# ZYNQ_POWER.net
KiCad netlist of a schematic drawn in Altium Designer
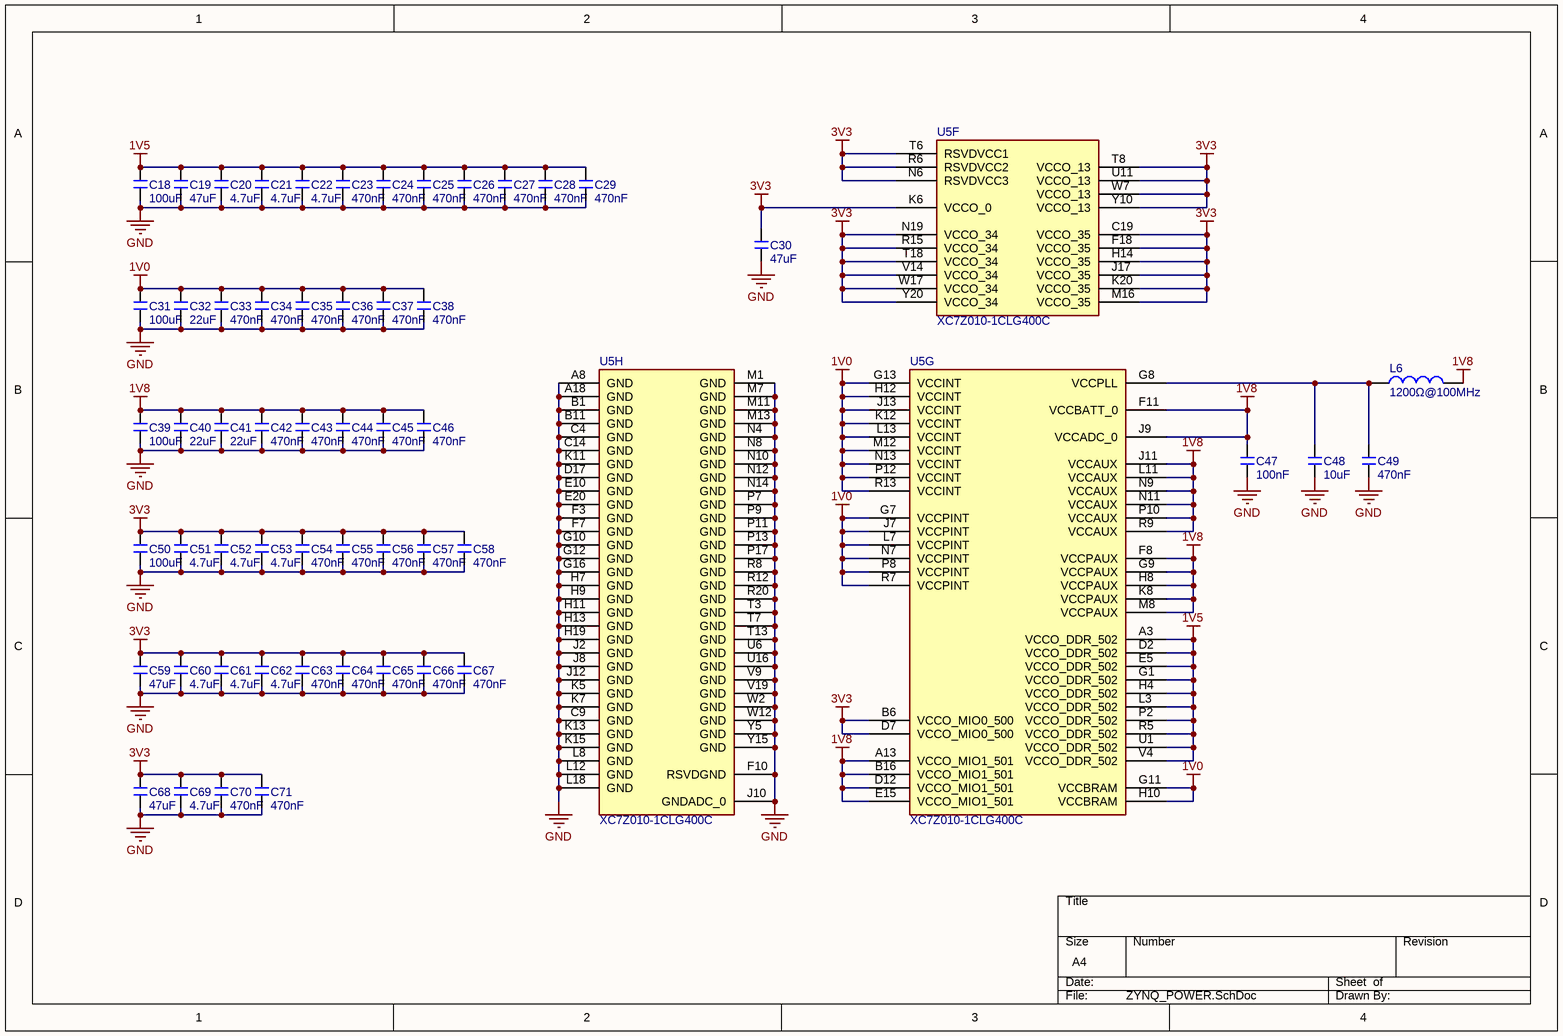
[diagram p0: ZYNQ_POWER.SchDoc]

(export (version "E")
  (design (tool "Eeschema 10.0.6"))
  (components
    (comp (ref "C18")
      (value "100uF")
      (footprint "C 0805_L")
      (description "无极性贴片电容")
      (fields (field (name "版权归属") "源创客"))
      (libsource (lib "3.1   - 电阻-电容-电感") (part "C"))
    )
    (comp (ref "C19")
      (value "47uF")
      (footprint "C 0805_L")
      (description "无极性贴片电容")
      (fields (field (name "版权归属") "源创客"))
      (libsource (lib "3.1   - 电阻-电容-电感") (part "C"))
    )
    (comp (ref "C20")
      (value "4.7uF")
      (footprint "C 0603_L")
      (description "无极性贴片电容")
      (fields (field (name "版权归属") "源创客"))
      (libsource (lib "3.1   - 电阻-电容-电感") (part "C"))
    )
    (comp (ref "C21")
      (value "4.7uF")
      (footprint "C 0603_L")
      (description "无极性贴片电容")
      (fields (field (name "版权归属") "源创客"))
      (libsource (lib "3.1   - 电阻-电容-电感") (part "C"))
    )
    (comp (ref "C22")
      (value "4.7uF")
      (footprint "C 0603_L")
      (description "无极性贴片电容")
      (fields (field (name "版权归属") "源创客"))
      (libsource (lib "3.1   - 电阻-电容-电感") (part "C"))
    )
    (comp (ref "C23")
      (value "470nF")
      (footprint "C 0805_L")
      (description "无极性贴片电容")
      (fields (field (name "版权归属") "源创客"))
      (libsource (lib "3.1   - 电阻-电容-电感") (part "C"))
    )
    (comp (ref "C24")
      (value "470nF")
      (footprint "C 0805_L")
      (description "无极性贴片电容")
      (fields (field (name "版权归属") "源创客"))
      (libsource (lib "3.1   - 电阻-电容-电感") (part "C"))
    )
    (comp (ref "C25")
      (value "470nF")
      (footprint "C 0805_L")
      (description "无极性贴片电容")
      (fields (field (name "版权归属") "源创客"))
      (libsource (lib "3.1   - 电阻-电容-电感") (part "C"))
    )
    (comp (ref "C26")
      (value "470nF")
      (footprint "C 0805_L")
      (description "无极性贴片电容")
      (fields (field (name "版权归属") "源创客"))
      (libsource (lib "3.1   - 电阻-电容-电感") (part "C"))
    )
    (comp (ref "C27")
      (value "470nF")
      (footprint "C 0805_L")
      (description "无极性贴片电容")
      (fields (field (name "版权归属") "源创客"))
      (libsource (lib "3.1   - 电阻-电容-电感") (part "C"))
    )
    (comp (ref "C28")
      (value "470nF")
      (footprint "C 0805_L")
      (description "无极性贴片电容")
      (fields (field (name "版权归属") "源创客"))
      (libsource (lib "3.1   - 电阻-电容-电感") (part "C"))
    )
    (comp (ref "C29")
      (value "470nF")
      (footprint "C 0805_L")
      (description "无极性贴片电容")
      (fields (field (name "版权归属") "源创客"))
      (libsource (lib "3.1   - 电阻-电容-电感") (part "C"))
    )
    (comp (ref "C30")
      (value "47uF")
      (footprint "C 0805_L")
      (description "无极性贴片电容")
      (fields (field (name "版权归属") "源创客"))
      (libsource (lib "3.1   - 电阻-电容-电感") (part "C"))
    )
    (comp (ref "C31")
      (value "100uF")
      (footprint "C 0805_L")
      (description "无极性贴片电容")
      (fields (field (name "版权归属") "源创客"))
      (libsource (lib "3.1   - 电阻-电容-电感") (part "C"))
    )
    (comp (ref "C32")
      (value "22uF")
      (footprint "C 0805_L")
      (description "无极性贴片电容")
      (fields (field (name "版权归属") "源创客"))
      (libsource (lib "3.1   - 电阻-电容-电感") (part "C"))
    )
    (comp (ref "C33")
      (value "470nF")
      (footprint "C 0805_L")
      (description "无极性贴片电容")
      (fields (field (name "版权归属") "源创客"))
      (libsource (lib "3.1   - 电阻-电容-电感") (part "C"))
    )
    (comp (ref "C34")
      (value "470nF")
      (footprint "C 0805_L")
      (description "无极性贴片电容")
      (fields (field (name "版权归属") "源创客"))
      (libsource (lib "3.1   - 电阻-电容-电感") (part "C"))
    )
    (comp (ref "C35")
      (value "470nF")
      (footprint "C 0805_L")
      (description "无极性贴片电容")
      (fields (field (name "版权归属") "源创客"))
      (libsource (lib "3.1   - 电阻-电容-电感") (part "C"))
    )
    (comp (ref "C36")
      (value "470nF")
      (footprint "C 0805_L")
      (description "无极性贴片电容")
      (fields (field (name "版权归属") "源创客"))
      (libsource (lib "3.1   - 电阻-电容-电感") (part "C"))
    )
    (comp (ref "C37")
      (value "470nF")
      (footprint "C 0805_L")
      (description "无极性贴片电容")
      (fields (field (name "版权归属") "源创客"))
      (libsource (lib "3.1   - 电阻-电容-电感") (part "C"))
    )
    (comp (ref "C38")
      (value "470nF")
      (footprint "C 0805_L")
      (description "无极性贴片电容")
      (fields (field (name "版权归属") "源创客"))
      (libsource (lib "3.1   - 电阻-电容-电感") (part "C"))
    )
    (comp (ref "C39")
      (value "100uF")
      (footprint "C 0805_L")
      (description "无极性贴片电容")
      (fields (field (name "版权归属") "源创客"))
      (libsource (lib "3.1   - 电阻-电容-电感") (part "C"))
    )
    (comp (ref "C40")
      (value "22uF")
      (footprint "C 0805_L")
      (description "无极性贴片电容")
      (fields (field (name "版权归属") "源创客"))
      (libsource (lib "3.1   - 电阻-电容-电感") (part "C"))
    )
    (comp (ref "C41")
      (value "22uF")
      (footprint "C 0805_L")
      (description "无极性贴片电容")
      (fields (field (name "版权归属") "源创客"))
      (libsource (lib "3.1   - 电阻-电容-电感") (part "C"))
    )
    (comp (ref "C42")
      (value "470nF")
      (footprint "C 0805_L")
      (description "无极性贴片电容")
      (fields (field (name "版权归属") "源创客"))
      (libsource (lib "3.1   - 电阻-电容-电感") (part "C"))
    )
    (comp (ref "C43")
      (value "470nF")
      (footprint "C 0805_L")
      (description "无极性贴片电容")
      (fields (field (name "版权归属") "源创客"))
      (libsource (lib "3.1   - 电阻-电容-电感") (part "C"))
    )
    (comp (ref "C44")
      (value "470nF")
      (footprint "C 0805_L")
      (description "无极性贴片电容")
      (fields (field (name "版权归属") "源创客"))
      (libsource (lib "3.1   - 电阻-电容-电感") (part "C"))
    )
    (comp (ref "C45")
      (value "470nF")
      (footprint "C 0805_L")
      (description "无极性贴片电容")
      (fields (field (name "版权归属") "源创客"))
      (libsource (lib "3.1   - 电阻-电容-电感") (part "C"))
    )
    (comp (ref "C46")
      (value "470nF")
      (footprint "C 0805_L")
      (description "无极性贴片电容")
      (fields (field (name "版权归属") "源创客"))
      (libsource (lib "3.1   - 电阻-电容-电感") (part "C"))
    )
    (comp (ref "C47")
      (value "100nF")
      (footprint "C 0402_L")
      (description "无极性贴片电容")
      (fields (field (name "版权归属") "源创客"))
      (libsource (lib "3.1   - 电阻-电容-电感") (part "C"))
    )
    (comp (ref "C48")
      (value "10uF")
      (footprint "C 0603_L")
      (description "无极性贴片电容")
      (fields (field (name "版权归属") "源创客"))
      (libsource (lib "3.1   - 电阻-电容-电感") (part "C"))
    )
    (comp (ref "C49")
      (value "470nF")
      (footprint "C 0805_L")
      (description "无极性贴片电容")
      (fields (field (name "版权归属") "源创客"))
      (libsource (lib "3.1   - 电阻-电容-电感") (part "C"))
    )
    (comp (ref "C50")
      (value "100uF")
      (footprint "C 0805_L")
      (description "无极性贴片电容")
      (fields (field (name "版权归属") "源创客"))
      (libsource (lib "3.1   - 电阻-电容-电感") (part "C"))
    )
    (comp (ref "C51")
      (value "4.7uF")
      (footprint "C 0603_L")
      (description "无极性贴片电容")
      (fields (field (name "版权归属") "源创客"))
      (libsource (lib "3.1   - 电阻-电容-电感") (part "C"))
    )
    (comp (ref "C52")
      (value "4.7uF")
      (footprint "C 0603_L")
      (description "无极性贴片电容")
      (fields (field (name "版权归属") "源创客"))
      (libsource (lib "3.1   - 电阻-电容-电感") (part "C"))
    )
    (comp (ref "C53")
      (value "4.7uF")
      (footprint "C 0603_L")
      (description "无极性贴片电容")
      (fields (field (name "版权归属") "源创客"))
      (libsource (lib "3.1   - 电阻-电容-电感") (part "C"))
    )
    (comp (ref "C54")
      (value "470nF")
      (footprint "C 0805_L")
      (description "无极性贴片电容")
      (fields (field (name "版权归属") "源创客"))
      (libsource (lib "3.1   - 电阻-电容-电感") (part "C"))
    )
    (comp (ref "C55")
      (value "470nF")
      (footprint "C 0805_L")
      (description "无极性贴片电容")
      (fields (field (name "版权归属") "源创客"))
      (libsource (lib "3.1   - 电阻-电容-电感") (part "C"))
    )
    (comp (ref "C56")
      (value "470nF")
      (footprint "C 0805_L")
      (description "无极性贴片电容")
      (fields (field (name "版权归属") "源创客"))
      (libsource (lib "3.1   - 电阻-电容-电感") (part "C"))
    )
    (comp (ref "C57")
      (value "470nF")
      (footprint "C 0805_L")
      (description "无极性贴片电容")
      (fields (field (name "版权归属") "源创客"))
      (libsource (lib "3.1   - 电阻-电容-电感") (part "C"))
    )
    (comp (ref "C58")
      (value "470nF")
      (footprint "C 0805_L")
      (description "无极性贴片电容")
      (fields (field (name "版权归属") "源创客"))
      (libsource (lib "3.1   - 电阻-电容-电感") (part "C"))
    )
    (comp (ref "C59")
      (value "47uF")
      (footprint "C 0805_L")
      (description "无极性贴片电容")
      (fields (field (name "版权归属") "源创客"))
      (libsource (lib "3.1   - 电阻-电容-电感") (part "C"))
    )
    (comp (ref "C60")
      (value "4.7uF")
      (footprint "C 0603_L")
      (description "无极性贴片电容")
      (fields (field (name "版权归属") "源创客"))
      (libsource (lib "3.1   - 电阻-电容-电感") (part "C"))
    )
    (comp (ref "C61")
      (value "4.7uF")
      (footprint "C 0603_L")
      (description "无极性贴片电容")
      (fields (field (name "版权归属") "源创客"))
      (libsource (lib "3.1   - 电阻-电容-电感") (part "C"))
    )
    (comp (ref "C62")
      (value "4.7uF")
      (footprint "C 0603_L")
      (description "无极性贴片电容")
      (fields (field (name "版权归属") "源创客"))
      (libsource (lib "3.1   - 电阻-电容-电感") (part "C"))
    )
    (comp (ref "C63")
      (value "470nF")
      (footprint "C 0805_L")
      (description "无极性贴片电容")
      (fields (field (name "版权归属") "源创客"))
      (libsource (lib "3.1   - 电阻-电容-电感") (part "C"))
    )
    (comp (ref "C64")
      (value "470nF")
      (footprint "C 0805_L")
      (description "无极性贴片电容")
      (fields (field (name "版权归属") "源创客"))
      (libsource (lib "3.1   - 电阻-电容-电感") (part "C"))
    )
    (comp (ref "C65")
      (value "470nF")
      (footprint "C 0805_L")
      (description "无极性贴片电容")
      (fields (field (name "版权归属") "源创客"))
      (libsource (lib "3.1   - 电阻-电容-电感") (part "C"))
    )
    (comp (ref "C66")
      (value "470nF")
      (footprint "C 0805_L")
      (description "无极性贴片电容")
      (fields (field (name "版权归属") "源创客"))
      (libsource (lib "3.1   - 电阻-电容-电感") (part "C"))
    )
    (comp (ref "C67")
      (value "470nF")
      (footprint "C 0805_L")
      (description "无极性贴片电容")
      (fields (field (name "版权归属") "源创客"))
      (libsource (lib "3.1   - 电阻-电容-电感") (part "C"))
    )
    (comp (ref "C68")
      (value "47uF")
      (footprint "C 0805_L")
      (description "无极性贴片电容")
      (fields (field (name "版权归属") "源创客"))
      (libsource (lib "3.1   - 电阻-电容-电感") (part "C"))
    )
    (comp (ref "C69")
      (value "4.7uF")
      (footprint "C 0603_L")
      (description "无极性贴片电容")
      (fields (field (name "版权归属") "源创客"))
      (libsource (lib "3.1   - 电阻-电容-电感") (part "C"))
    )
    (comp (ref "C70")
      (value "470nF")
      (footprint "C 0805_L")
      (description "无极性贴片电容")
      (fields (field (name "版权归属") "源创客"))
      (libsource (lib "3.1   - 电阻-电容-电感") (part "C"))
    )
    (comp (ref "C71")
      (value "470nF")
      (footprint "C 0805_L")
      (description "无极性贴片电容")
      (fields (field (name "版权归属") "源创客"))
      (libsource (lib "3.1   - 电阻-电容-电感") (part "C"))
    )
    (comp (ref "L6")
      (value "1200Ω@100MHz")
      (footprint "L 0805")
      (description "小功率贴片电感")
      (fields (field (name "版权归属") "源创客"))
      (libsource (lib "3.1   - 电阻-电容-电感") (part "L"))
    )
    (comp (ref "U5")
      (value "XC7Z010-1CLG400C")
      (footprint "CLG400")
      (description "ZYNQ7000芯片")
      (libsource (lib "16.2 - Xilinx芯片") (part "XC7Z010-1CLG400C"))
    )
  )
  (nets
    (net (code "1") (name "1V0") (class "Default")
      (node (ref "C31") (pin "1") (pinfunction "1_1") (pintype "passive"))
      (node (ref "C32") (pin "2") (pinfunction "2_2") (pintype "passive"))
      (node (ref "C33") (pin "2") (pinfunction "2_2") (pintype "passive"))
      (node (ref "C34") (pin "2") (pinfunction "2_2") (pintype "passive"))
      (node (ref "C35") (pin "2") (pinfunction "2_2") (pintype "passive"))
      (node (ref "C36") (pin "2") (pinfunction "2_2") (pintype "passive"))
      (node (ref "C37") (pin "2") (pinfunction "2_2") (pintype "passive"))
      (node (ref "C38") (pin "2") (pinfunction "2_2") (pintype "passive"))
      (node (ref "U5") (pin "G11") (pinfunction "VCCBRAM_G11") (pintype "power_in"))
      (node (ref "U5") (pin "G13") (pinfunction "VCCINT_G13") (pintype "power_in"))
      (node (ref "U5") (pin "G7") (pinfunction "VCCPINT_G7") (pintype "power_in"))
      (node (ref "U5") (pin "H10") (pinfunction "VCCBRAM_H10") (pintype "power_in"))
      (node (ref "U5") (pin "H12") (pinfunction "VCCINT_H12") (pintype "power_in"))
      (node (ref "U5") (pin "J13") (pinfunction "VCCINT_J13") (pintype "power_in"))
      (node (ref "U5") (pin "J7") (pinfunction "VCCPINT_J7") (pintype "power_in"))
      (node (ref "U5") (pin "K12") (pinfunction "VCCINT_K12") (pintype "power_in"))
      (node (ref "U5") (pin "L13") (pinfunction "VCCINT_L13") (pintype "power_in"))
      (node (ref "U5") (pin "L7") (pinfunction "VCCPINT_L7") (pintype "power_in"))
      (node (ref "U5") (pin "M12") (pinfunction "VCCINT_M12") (pintype "power_in"))
      (node (ref "U5") (pin "N13") (pinfunction "VCCINT_N13") (pintype "power_in"))
      (node (ref "U5") (pin "N7") (pinfunction "VCCPINT_N7") (pintype "power_in"))
      (node (ref "U5") (pin "P12") (pinfunction "VCCINT_P12") (pintype "power_in"))
      (node (ref "U5") (pin "P8") (pinfunction "VCCPINT_P8") (pintype "power_in"))
      (node (ref "U5") (pin "R13") (pinfunction "VCCINT_R13") (pintype "power_in"))
      (node (ref "U5") (pin "R7") (pinfunction "VCCPINT_R7") (pintype "power_in"))
    )
    (net (code "2") (name "1V5") (class "Default")
      (node (ref "C18") (pin "1") (pinfunction "1_1") (pintype "passive"))
      (node (ref "C19") (pin "2") (pinfunction "2_2") (pintype "passive"))
      (node (ref "C20") (pin "2") (pinfunction "2_2") (pintype "passive"))
      (node (ref "C21") (pin "2") (pinfunction "2_2") (pintype "passive"))
      (node (ref "C22") (pin "2") (pinfunction "2_2") (pintype "passive"))
      (node (ref "C23") (pin "2") (pinfunction "2_2") (pintype "passive"))
      (node (ref "C24") (pin "2") (pinfunction "2_2") (pintype "passive"))
      (node (ref "C25") (pin "2") (pinfunction "2_2") (pintype "passive"))
      (node (ref "C26") (pin "2") (pinfunction "2_2") (pintype "passive"))
      (node (ref "C27") (pin "2") (pinfunction "2_2") (pintype "passive"))
      (node (ref "C28") (pin "2") (pinfunction "2_2") (pintype "passive"))
      (node (ref "C29") (pin "2") (pinfunction "2_2") (pintype "passive"))
      (node (ref "U5") (pin "A3") (pinfunction "VCCO_DDR_502_A3") (pintype "power_in"))
      (node (ref "U5") (pin "D2") (pinfunction "VCCO_DDR_502_D2") (pintype "power_in"))
      (node (ref "U5") (pin "E5") (pinfunction "VCCO_DDR_502_E5") (pintype "power_in"))
      (node (ref "U5") (pin "G1") (pinfunction "VCCO_DDR_502_G1") (pintype "power_in"))
      (node (ref "U5") (pin "H4") (pinfunction "VCCO_DDR_502_H4") (pintype "power_in"))
      (node (ref "U5") (pin "L3") (pinfunction "VCCO_DDR_502_L3") (pintype "power_in"))
      (node (ref "U5") (pin "P2") (pinfunction "VCCO_DDR_502_P2") (pintype "power_in"))
      (node (ref "U5") (pin "R5") (pinfunction "VCCO_DDR_502_R5") (pintype "power_in"))
      (node (ref "U5") (pin "U1") (pinfunction "VCCO_DDR_502_U1") (pintype "power_in"))
      (node (ref "U5") (pin "V4") (pinfunction "VCCO_DDR_502_V4") (pintype "power_in"))
    )
    (net (code "3") (name "1V8") (class "Default")
      (node (ref "C39") (pin "1") (pinfunction "1_1") (pintype "passive"))
      (node (ref "C40") (pin "2") (pinfunction "2_2") (pintype "passive"))
      (node (ref "C41") (pin "2") (pinfunction "2_2") (pintype "passive"))
      (node (ref "C42") (pin "2") (pinfunction "2_2") (pintype "passive"))
      (node (ref "C43") (pin "2") (pinfunction "2_2") (pintype "passive"))
      (node (ref "C44") (pin "2") (pinfunction "2_2") (pintype "passive"))
      (node (ref "C45") (pin "2") (pinfunction "2_2") (pintype "passive"))
      (node (ref "C46") (pin "2") (pinfunction "2_2") (pintype "passive"))
      (node (ref "C47") (pin "2") (pinfunction "2_2") (pintype "passive"))
      (node (ref "L6") (pin "2") (pinfunction "2_2") (pintype "passive"))
      (node (ref "U5") (pin "A13") (pinfunction "VCCO_MIO1_501_A13") (pintype "power_in"))
      (node (ref "U5") (pin "B16") (pinfunction "VCCO_MIO1_501_B16") (pintype "power_in"))
      (node (ref "U5") (pin "D12") (pinfunction "VCCO_MIO1_501_D12") (pintype "power_in"))
      (node (ref "U5") (pin "E15") (pinfunction "VCCO_MIO1_501_E15") (pintype "power_in"))
      (node (ref "U5") (pin "F11") (pinfunction "VCCBATT_0_F11") (pintype "power_in"))
      (node (ref "U5") (pin "F8") (pinfunction "VCCPAUX_F8") (pintype "power_in"))
      (node (ref "U5") (pin "G9") (pinfunction "VCCPAUX_G9") (pintype "power_in"))
      (node (ref "U5") (pin "H8") (pinfunction "VCCPAUX_H8") (pintype "power_in"))
      (node (ref "U5") (pin "J11") (pinfunction "VCCAUX_J11") (pintype "power_in"))
      (node (ref "U5") (pin "J9") (pinfunction "VCCADC_0_J9") (pintype "power_in"))
      (node (ref "U5") (pin "K8") (pinfunction "VCCPAUX_K8") (pintype "power_in"))
      (node (ref "U5") (pin "L11") (pinfunction "VCCAUX_L11") (pintype "power_in"))
      (node (ref "U5") (pin "M8") (pinfunction "VCCPAUX_M8") (pintype "power_in"))
      (node (ref "U5") (pin "N11") (pinfunction "VCCAUX_N11") (pintype "power_in"))
      (node (ref "U5") (pin "N9") (pinfunction "VCCAUX_N9") (pintype "power_in"))
      (node (ref "U5") (pin "P10") (pinfunction "VCCAUX_P10") (pintype "power_in"))
      (node (ref "U5") (pin "R9") (pinfunction "VCCAUX_R9") (pintype "power_in"))
    )
    (net (code "4") (name "3V3") (class "Default")
      (node (ref "C30") (pin "2") (pinfunction "2_2") (pintype "passive"))
      (node (ref "C50") (pin "1") (pinfunction "1_1") (pintype "passive"))
      (node (ref "C51") (pin "2") (pinfunction "2_2") (pintype "passive"))
      (node (ref "C52") (pin "2") (pinfunction "2_2") (pintype "passive"))
      (node (ref "C53") (pin "2") (pinfunction "2_2") (pintype "passive"))
      (node (ref "C54") (pin "2") (pinfunction "2_2") (pintype "passive"))
      (node (ref "C55") (pin "2") (pinfunction "2_2") (pintype "passive"))
      (node (ref "C56") (pin "2") (pinfunction "2_2") (pintype "passive"))
      (node (ref "C57") (pin "2") (pinfunction "2_2") (pintype "passive"))
      (node (ref "C58") (pin "2") (pinfunction "2_2") (pintype "passive"))
      (node (ref "C59") (pin "1") (pinfunction "1_1") (pintype "passive"))
      (node (ref "C60") (pin "2") (pinfunction "2_2") (pintype "passive"))
      (node (ref "C61") (pin "2") (pinfunction "2_2") (pintype "passive"))
      (node (ref "C62") (pin "2") (pinfunction "2_2") (pintype "passive"))
      (node (ref "C63") (pin "2") (pinfunction "2_2") (pintype "passive"))
      (node (ref "C64") (pin "2") (pinfunction "2_2") (pintype "passive"))
      (node (ref "C65") (pin "2") (pinfunction "2_2") (pintype "passive"))
      (node (ref "C66") (pin "2") (pinfunction "2_2") (pintype "passive"))
      (node (ref "C67") (pin "2") (pinfunction "2_2") (pintype "passive"))
      (node (ref "C68") (pin "1") (pinfunction "1_1") (pintype "passive"))
      (node (ref "C69") (pin "2") (pinfunction "2_2") (pintype "passive"))
      (node (ref "C70") (pin "2") (pinfunction "2_2") (pintype "passive"))
      (node (ref "C71") (pin "2") (pinfunction "2_2") (pintype "passive"))
      (node (ref "U5") (pin "B6") (pinfunction "VCCO_MIO0_500_B6") (pintype "power_in"))
      (node (ref "U5") (pin "C19") (pinfunction "VCCO_35_C19") (pintype "power_in"))
      (node (ref "U5") (pin "D7") (pinfunction "VCCO_MIO0_500_D7") (pintype "power_in"))
      (node (ref "U5") (pin "F18") (pinfunction "VCCO_35_F18") (pintype "power_in"))
      (node (ref "U5") (pin "H14") (pinfunction "VCCO_35_H14") (pintype "power_in"))
      (node (ref "U5") (pin "J17") (pinfunction "VCCO_35_J17") (pintype "power_in"))
      (node (ref "U5") (pin "K20") (pinfunction "VCCO_35_K20") (pintype "power_in"))
      (node (ref "U5") (pin "K6") (pinfunction "VCCO_0_K6") (pintype "power_in"))
      (node (ref "U5") (pin "M16") (pinfunction "VCCO_35_M16") (pintype "power_in"))
      (node (ref "U5") (pin "N19") (pinfunction "VCCO_34_N19") (pintype "power_in"))
      (node (ref "U5") (pin "N6") (pinfunction "RSVDVCC3_N6") (pintype "power_in"))
      (node (ref "U5") (pin "R15") (pinfunction "VCCO_34_R15") (pintype "power_in"))
      (node (ref "U5") (pin "R6") (pinfunction "RSVDVCC2_R6") (pintype "power_in"))
      (node (ref "U5") (pin "T18") (pinfunction "VCCO_34_T18") (pintype "power_in"))
      (node (ref "U5") (pin "T6") (pinfunction "RSVDVCC1_T6") (pintype "power_in"))
      (node (ref "U5") (pin "T8") (pinfunction "VCCO_13_T8") (pintype "power_in"))
      (node (ref "U5") (pin "U11") (pinfunction "VCCO_13_U11") (pintype "power_in"))
      (node (ref "U5") (pin "V14") (pinfunction "VCCO_34_V14") (pintype "power_in"))
      (node (ref "U5") (pin "W17") (pinfunction "VCCO_34_W17") (pintype "power_in"))
      (node (ref "U5") (pin "W7") (pinfunction "VCCO_13_W7") (pintype "power_in"))
      (node (ref "U5") (pin "Y10") (pinfunction "VCCO_13_Y10") (pintype "power_in"))
      (node (ref "U5") (pin "Y20") (pinfunction "VCCO_34_Y20") (pintype "power_in"))
    )
    (net (code "5") (name "GND") (class "Default")
      (node (ref "C18") (pin "2") (pinfunction "2_2") (pintype "passive"))
      (node (ref "C19") (pin "1") (pinfunction "1_1") (pintype "passive"))
      (node (ref "C20") (pin "1") (pinfunction "1_1") (pintype "passive"))
      (node (ref "C21") (pin "1") (pinfunction "1_1") (pintype "passive"))
      (node (ref "C22") (pin "1") (pinfunction "1_1") (pintype "passive"))
      (node (ref "C23") (pin "1") (pinfunction "1_1") (pintype "passive"))
      (node (ref "C24") (pin "1") (pinfunction "1_1") (pintype "passive"))
      (node (ref "C25") (pin "1") (pinfunction "1_1") (pintype "passive"))
      (node (ref "C26") (pin "1") (pinfunction "1_1") (pintype "passive"))
      (node (ref "C27") (pin "1") (pinfunction "1_1") (pintype "passive"))
      (node (ref "C28") (pin "1") (pinfunction "1_1") (pintype "passive"))
      (node (ref "C29") (pin "1") (pinfunction "1_1") (pintype "passive"))
      (node (ref "C30") (pin "1") (pinfunction "1_1") (pintype "passive"))
      (node (ref "C31") (pin "2") (pinfunction "2_2") (pintype "passive"))
      (node (ref "C32") (pin "1") (pinfunction "1_1") (pintype "passive"))
      (node (ref "C33") (pin "1") (pinfunction "1_1") (pintype "passive"))
      (node (ref "C34") (pin "1") (pinfunction "1_1") (pintype "passive"))
      (node (ref "C35") (pin "1") (pinfunction "1_1") (pintype "passive"))
      (node (ref "C36") (pin "1") (pinfunction "1_1") (pintype "passive"))
      (node (ref "C37") (pin "1") (pinfunction "1_1") (pintype "passive"))
      (node (ref "C38") (pin "1") (pinfunction "1_1") (pintype "passive"))
      (node (ref "C39") (pin "2") (pinfunction "2_2") (pintype "passive"))
      (node (ref "C40") (pin "1") (pinfunction "1_1") (pintype "passive"))
      (node (ref "C41") (pin "1") (pinfunction "1_1") (pintype "passive"))
      (node (ref "C42") (pin "1") (pinfunction "1_1") (pintype "passive"))
      (node (ref "C43") (pin "1") (pinfunction "1_1") (pintype "passive"))
      (node (ref "C44") (pin "1") (pinfunction "1_1") (pintype "passive"))
      (node (ref "C45") (pin "1") (pinfunction "1_1") (pintype "passive"))
      (node (ref "C46") (pin "1") (pinfunction "1_1") (pintype "passive"))
      (node (ref "C47") (pin "1") (pinfunction "1_1") (pintype "passive"))
      (node (ref "C48") (pin "1") (pinfunction "1_1") (pintype "passive"))
      (node (ref "C49") (pin "1") (pinfunction "1_1") (pintype "passive"))
      (node (ref "C50") (pin "2") (pinfunction "2_2") (pintype "passive"))
      (node (ref "C51") (pin "1") (pinfunction "1_1") (pintype "passive"))
      (node (ref "C52") (pin "1") (pinfunction "1_1") (pintype "passive"))
      (node (ref "C53") (pin "1") (pinfunction "1_1") (pintype "passive"))
      (node (ref "C54") (pin "1") (pinfunction "1_1") (pintype "passive"))
      (node (ref "C55") (pin "1") (pinfunction "1_1") (pintype "passive"))
      (node (ref "C56") (pin "1") (pinfunction "1_1") (pintype "passive"))
      (node (ref "C57") (pin "1") (pinfunction "1_1") (pintype "passive"))
      (node (ref "C58") (pin "1") (pinfunction "1_1") (pintype "passive"))
      (node (ref "C59") (pin "2") (pinfunction "2_2") (pintype "passive"))
      (node (ref "C60") (pin "1") (pinfunction "1_1") (pintype "passive"))
      (node (ref "C61") (pin "1") (pinfunction "1_1") (pintype "passive"))
      (node (ref "C62") (pin "1") (pinfunction "1_1") (pintype "passive"))
      (node (ref "C63") (pin "1") (pinfunction "1_1") (pintype "passive"))
      (node (ref "C64") (pin "1") (pinfunction "1_1") (pintype "passive"))
      (node (ref "C65") (pin "1") (pinfunction "1_1") (pintype "passive"))
      (node (ref "C66") (pin "1") (pinfunction "1_1") (pintype "passive"))
      (node (ref "C67") (pin "1") (pinfunction "1_1") (pintype "passive"))
      (node (ref "C68") (pin "2") (pinfunction "2_2") (pintype "passive"))
      (node (ref "C69") (pin "1") (pinfunction "1_1") (pintype "passive"))
      (node (ref "C70") (pin "1") (pinfunction "1_1") (pintype "passive"))
      (node (ref "C71") (pin "1") (pinfunction "1_1") (pintype "passive"))
      (node (ref "U5") (pin "A18") (pinfunction "GND_A18") (pintype "power_in"))
      (node (ref "U5") (pin "A8") (pinfunction "GND_A8") (pintype "power_in"))
      (node (ref "U5") (pin "B1") (pinfunction "GND_B1") (pintype "power_in"))
      (node (ref "U5") (pin "B11") (pinfunction "GND_B11") (pintype "power_in"))
      (node (ref "U5") (pin "C14") (pinfunction "GND_C14") (pintype "power_in"))
      (node (ref "U5") (pin "C4") (pinfunction "GND_C4") (pintype "power_in"))
      (node (ref "U5") (pin "C9") (pinfunction "GND_C9") (pintype "power_in"))
      (node (ref "U5") (pin "D17") (pinfunction "GND_D17") (pintype "power_in"))
      (node (ref "U5") (pin "E10") (pinfunction "GND_E10") (pintype "power_in"))
      (node (ref "U5") (pin "E20") (pinfunction "GND_E20") (pintype "power_in"))
      (node (ref "U5") (pin "F10") (pinfunction "RSVDGND_F10") (pintype "power_in"))
      (node (ref "U5") (pin "F3") (pinfunction "GND_F3") (pintype "power_in"))
      (node (ref "U5") (pin "F7") (pinfunction "GND_F7") (pintype "power_in"))
      (node (ref "U5") (pin "G10") (pinfunction "GND_G10") (pintype "power_in"))
      (node (ref "U5") (pin "G12") (pinfunction "GND_G12") (pintype "power_in"))
      (node (ref "U5") (pin "G16") (pinfunction "GND_G16") (pintype "power_in"))
      (node (ref "U5") (pin "H11") (pinfunction "GND_H11") (pintype "power_in"))
      (node (ref "U5") (pin "H13") (pinfunction "GND_H13") (pintype "power_in"))
      (node (ref "U5") (pin "H19") (pinfunction "GND_H19") (pintype "power_in"))
      (node (ref "U5") (pin "H7") (pinfunction "GND_H7") (pintype "power_in"))
      (node (ref "U5") (pin "H9") (pinfunction "GND_H9") (pintype "power_in"))
      (node (ref "U5") (pin "J10") (pinfunction "GNDADC_0_J10") (pintype "power_in"))
      (node (ref "U5") (pin "J12") (pinfunction "GND_J12") (pintype "power_in"))
      (node (ref "U5") (pin "J2") (pinfunction "GND_J2") (pintype "power_in"))
      (node (ref "U5") (pin "J8") (pinfunction "GND_J8") (pintype "power_in"))
      (node (ref "U5") (pin "K11") (pinfunction "GND_K11") (pintype "power_in"))
      (node (ref "U5") (pin "K13") (pinfunction "GND_K13") (pintype "power_in"))
      (node (ref "U5") (pin "K15") (pinfunction "GND_K15") (pintype "power_in"))
      (node (ref "U5") (pin "K5") (pinfunction "GND_K5") (pintype "power_in"))
      (node (ref "U5") (pin "K7") (pinfunction "GND_K7") (pintype "power_in"))
      (node (ref "U5") (pin "L12") (pinfunction "GND_L12") (pintype "power_in"))
      (node (ref "U5") (pin "L18") (pinfunction "GND_L18") (pintype "power_in"))
      (node (ref "U5") (pin "L8") (pinfunction "GND_L8") (pintype "power_in"))
      (node (ref "U5") (pin "M1") (pinfunction "GND_M1") (pintype "power_in"))
      (node (ref "U5") (pin "M11") (pinfunction "GND_M11") (pintype "power_in"))
      (node (ref "U5") (pin "M13") (pinfunction "GND_M13") (pintype "power_in"))
      (node (ref "U5") (pin "M7") (pinfunction "GND_M7") (pintype "power_in"))
      (node (ref "U5") (pin "N10") (pinfunction "GND_N10") (pintype "power_in"))
      (node (ref "U5") (pin "N12") (pinfunction "GND_N12") (pintype "power_in"))
      (node (ref "U5") (pin "N14") (pinfunction "GND_N14") (pintype "power_in"))
      (node (ref "U5") (pin "N4") (pinfunction "GND_N4") (pintype "power_in"))
      (node (ref "U5") (pin "N8") (pinfunction "GND_N8") (pintype "power_in"))
      (node (ref "U5") (pin "P11") (pinfunction "GND_P11") (pintype "power_in"))
      (node (ref "U5") (pin "P13") (pinfunction "GND_P13") (pintype "power_in"))
      (node (ref "U5") (pin "P17") (pinfunction "GND_P17") (pintype "power_in"))
      (node (ref "U5") (pin "P7") (pinfunction "GND_P7") (pintype "power_in"))
      (node (ref "U5") (pin "P9") (pinfunction "GND_P9") (pintype "power_in"))
      (node (ref "U5") (pin "R12") (pinfunction "GND_R12") (pintype "power_in"))
      (node (ref "U5") (pin "R20") (pinfunction "GND_R20") (pintype "power_in"))
      (node (ref "U5") (pin "R8") (pinfunction "GND_R8") (pintype "power_in"))
      (node (ref "U5") (pin "T13") (pinfunction "GND_T13") (pintype "power_in"))
      (node (ref "U5") (pin "T3") (pinfunction "GND_T3") (pintype "power_in"))
      (node (ref "U5") (pin "T7") (pinfunction "GND_T7") (pintype "power_in"))
      (node (ref "U5") (pin "U16") (pinfunction "GND_U16") (pintype "power_in"))
      (node (ref "U5") (pin "U6") (pinfunction "GND_U6") (pintype "power_in"))
      (node (ref "U5") (pin "V19") (pinfunction "GND_V19") (pintype "power_in"))
      (node (ref "U5") (pin "V9") (pinfunction "GND_V9") (pintype "power_in"))
      (node (ref "U5") (pin "W12") (pinfunction "GND_W12") (pintype "power_in"))
      (node (ref "U5") (pin "W2") (pinfunction "GND_W2") (pintype "power_in"))
      (node (ref "U5") (pin "Y15") (pinfunction "GND_Y15") (pintype "power_in"))
      (node (ref "U5") (pin "Y5") (pinfunction "GND_Y5") (pintype "power_in"))
    )
    (net (code "6") (name "Net-(U5G-VCCPLL)") (class "Default")
      (node (ref "C48") (pin "2") (pinfunction "2_2") (pintype "passive"))
      (node (ref "C49") (pin "2") (pinfunction "2_2") (pintype "passive"))
      (node (ref "L6") (pin "1") (pinfunction "1_1") (pintype "passive"))
      (node (ref "U5") (pin "G8") (pinfunction "VCCPLL_G8") (pintype "power_in"))
    )
  )
)
